# 01POWER.net
KiCad netlist of a schematic drawn in Altium Designer
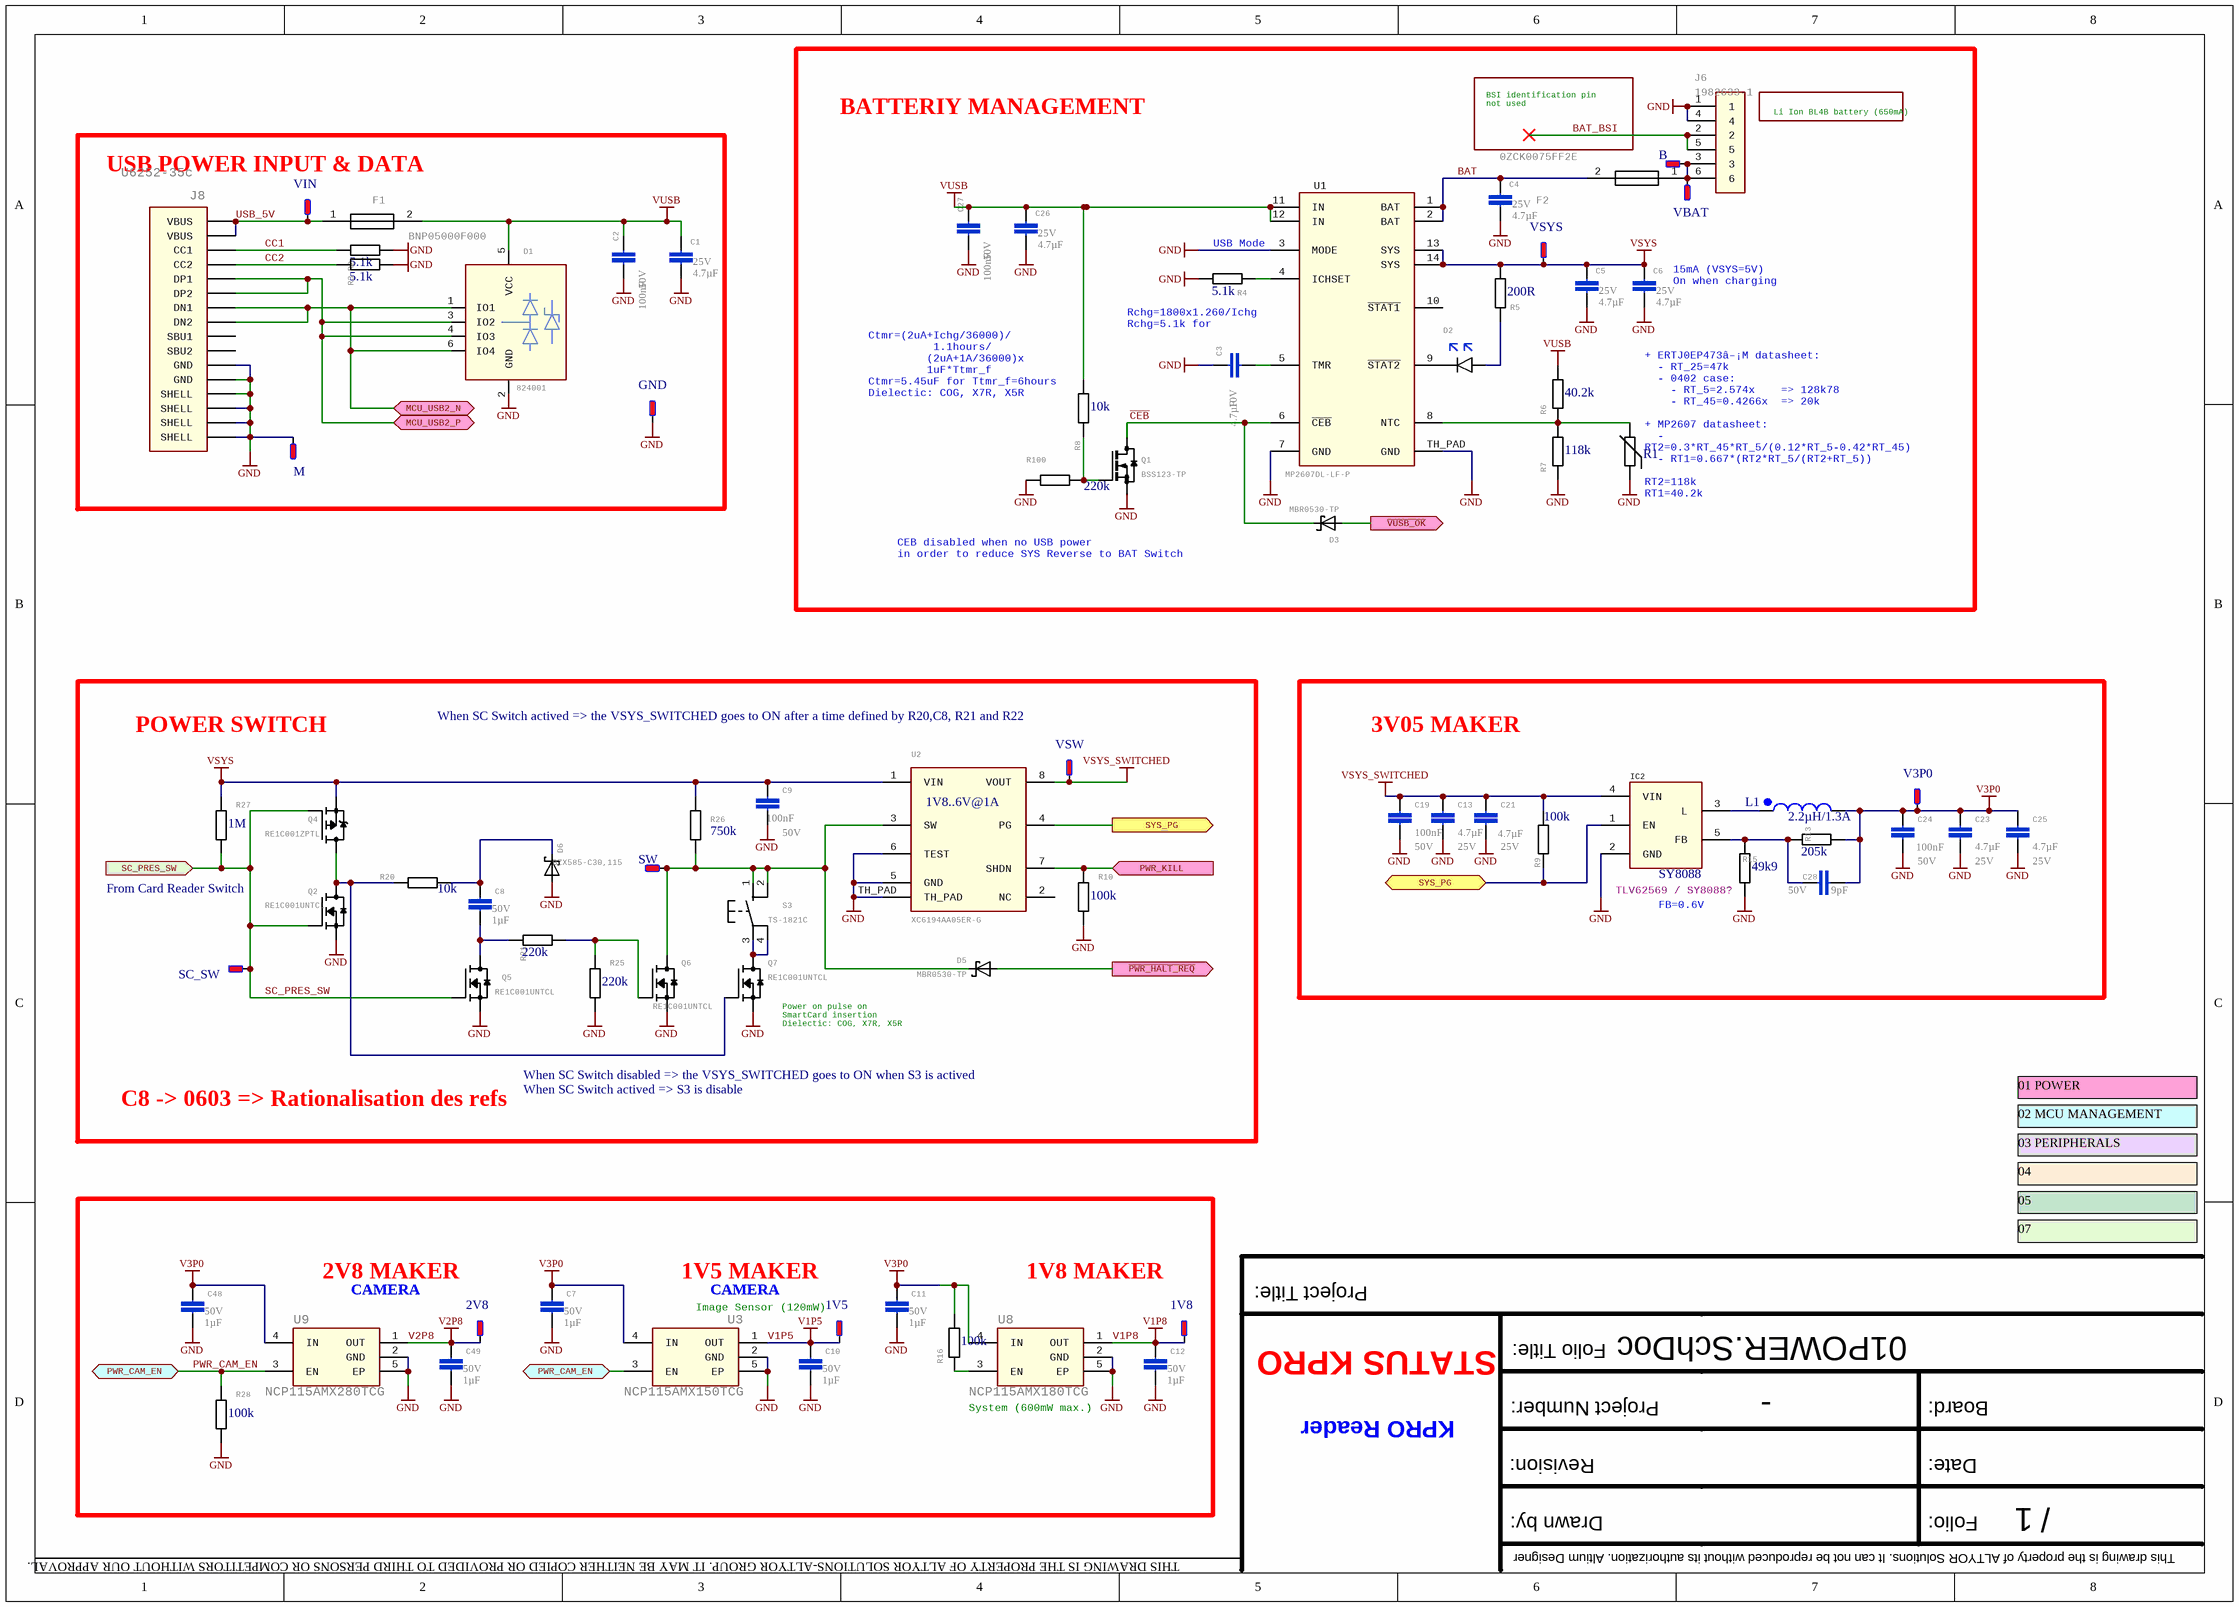
[diagram p0: 01POWER.SchDoc]

(export (version "E")
  (design (tool "Eeschema 10.0.6"))
  (components
    (comp (ref "1V5")
      (value "TP")
      (footprint "TESTPOINT 1MM")
      (description "Pointe de test 1.27mm")
      (libsource (lib "KCP-2282-600") (part "TP"))
    )
    (comp (ref "1V8")
      (value "TP")
      (footprint "TESTPOINT 1MM")
      (description "Pointe de test 1.27mm")
      (libsource (lib "KCP-2282-600") (part "TP"))
    )
    (comp (ref "2V8")
      (value "TP")
      (footprint "TESTPOINT 1MM")
      (description "Pointe de test 1.27mm")
      (libsource (lib "KCP-2282-600") (part "TP"))
    )
    (comp (ref "B")
      (value "TP")
      (footprint "PLAGE - ROUGE")
      (description "Pointe de test 1.27mm")
      (libsource (lib "KCP-2282-600") (part "TP"))
    )
    (comp (ref "C1")
      (value "0805X475M250CT")
      (footprint "0805 - CAPACITOR")
      (description "CAP X5R 4.7µF 25V ±10% 0805")
      (fields
        (field (name "MANUFACTURER") "WALSIN")
        (field (name "VOLTAGE") "25V")
        (field (name "NAME") "4.7µF")
      )
      (libsource (lib "KCP-2282-600") (part "C-EU-C4.7µF-X5R-6.3V-0805"))
    )
    (comp (ref "C2")
      (value "0402B104K500CT")
      (footprint "0402 - CAPACITOR")
      (description "CAP X7R 100nF 50V ±10% 0402")
      (fields
        (field (name "MANUFACTURER") "WALSIN")
        (field (name "VOLTAGE") "50V")
        (field (name "NAME") "100nF")
      )
      (libsource (lib "KCP-2282-600") (part "C-EU-C100NF-X7R-16V-0402"))
    )
    (comp (ref "C3")
      (value "CC0402KRX5R6BB475")
      (footprint "0402 - CAPACITOR")
      (description "CAP X5R 4.7µF 10V ±10% 0402")
      (fields
        (field (name "MANUFACTURER") "YAGEO")
        (field (name "VOLTAGE") "10V")
        (field (name "NAME") "4.7µF")
      )
      (libsource (lib "KCP-2282-600") (part "C-EU-C5UF-X7R-6.3V-0402"))
    )
    (comp (ref "C4")
      (value "0805X475M250CT")
      (footprint "0805 - CAPACITOR")
      (description "CAP X5R 4.7µF 25V ±10% 0805")
      (fields
        (field (name "MANUFACTURER") "WALSIN")
        (field (name "VOLTAGE") "25V")
        (field (name "NAME") "4.7µF")
      )
      (libsource (lib "KCP-2282-600") (part "C-EU-C4.7µF-X5R-6.3V-0805"))
    )
    (comp (ref "C5")
      (value "0805X475M250CT")
      (footprint "0805 - CAPACITOR")
      (description "CAP X5R 4.7µF 25V ±10% 0805")
      (fields
        (field (name "MANUFACTURER") "WALSIN")
        (field (name "VOLTAGE") "25V")
        (field (name "NAME") "4.7µF")
      )
      (libsource (lib "KCP-2282-600") (part "C-EU-C4.7µF-X5R-6.3V-0805"))
    )
    (comp (ref "C6")
      (value "0805X475M250CT")
      (footprint "0805 - CAPACITOR")
      (description "CAP X5R 4.7µF 25V ±10% 0805")
      (fields
        (field (name "MANUFACTURER") "WALSIN")
        (field (name "VOLTAGE") "25V")
        (field (name "NAME") "4.7µF")
      )
      (libsource (lib "KCP-2282-600") (part "C-EU-C4.7µF-X5R-6.3V-0805"))
    )
    (comp (ref "C7")
      (value "0603X105K500CT")
      (footprint "0603 - CAPACITOR")
      (description "CAP X5R 1µF 50V ±10% 0603")
      (fields
        (field (name "MANUFACTURER") "WALSIN")
        (field (name "VOLTAGE") "50V")
        (field (name "NAME") "1µF")
      )
      (libsource (lib "KCP-2282-600") (part "C-EU-C1µF-X5R-6.3V-0603"))
    )
    (comp (ref "C8")
      (value "0603X105K500CT")
      (footprint "0603 - CAPACITOR")
      (description "CAP X5R 1µF 50V ±10% 0603")
      (fields
        (field (name "MANUFACTURER") "WALSIN")
        (field (name "VOLTAGE") "50V")
        (field (name "NAME") "1µF")
      )
      (libsource (lib "KCP-2282-600") (part "C-EU-C1µF-X5R-6.3V-0603"))
    )
    (comp (ref "C9")
      (value "0402B104K500CT")
      (footprint "0402 - CAPACITOR")
      (description "CAP X7R 100nF 50V ±10% 0402")
      (fields
        (field (name "MANUFACTURER") "WALSIN")
        (field (name "VOLTAGE") "50V")
        (field (name "NAME") "100nF")
      )
      (libsource (lib "KCP-2282-600") (part "C-EU-C100NF-X7R-16V-0402"))
    )
    (comp (ref "C10")
      (value "0603X105K500CT")
      (footprint "0603 - CAPACITOR")
      (description "CAP X5R 1µF 50V ±10% 0603")
      (fields
        (field (name "MANUFACTURER") "WALSIN")
        (field (name "VOLTAGE") "50V")
        (field (name "NAME") "1µF")
      )
      (libsource (lib "KCP-2282-600") (part "C-EU-C1µF-X5R-6.3V-0603"))
    )
    (comp (ref "C11")
      (value "0603X105K500CT")
      (footprint "0603 - CAPACITOR")
      (description "CAP X5R 1µF 50V ±10% 0603")
      (fields
        (field (name "MANUFACTURER") "WALSIN")
        (field (name "VOLTAGE") "50V")
        (field (name "NAME") "1µF")
      )
      (libsource (lib "KCP-2282-600") (part "C-EU-C1µF-X5R-6.3V-0603"))
    )
    (comp (ref "C12")
      (value "0603X105K500CT")
      (footprint "0603 - CAPACITOR")
      (description "CAP X5R 1µF 50V ±10% 0603")
      (fields
        (field (name "MANUFACTURER") "WALSIN")
        (field (name "VOLTAGE") "50V")
        (field (name "NAME") "1µF")
      )
      (libsource (lib "KCP-2282-600") (part "C-EU-C1µF-X5R-6.3V-0603"))
    )
    (comp (ref "C13")
      (value "0805X475M250CT")
      (footprint "0805 - CAPACITOR")
      (description "CAP X5R 4.7µF 25V ±10% 0805")
      (fields
        (field (name "MANUFACTURER") "WALSIN")
        (field (name "VOLTAGE") "25V")
        (field (name "NAME") "4.7µF")
      )
      (libsource (lib "KCP-2282-600") (part "C-EU-C4.7µF-X5R-6.3V-0805"))
    )
    (comp (ref "C19")
      (value "0402B104K500CT")
      (footprint "0402 - CAPACITOR")
      (description "CAP X7R 100nF 50V ±10% 0402")
      (fields
        (field (name "MANUFACTURER") "WALSIN")
        (field (name "VOLTAGE") "50V")
        (field (name "NAME") "100nF")
      )
      (libsource (lib "KCP-2282-600") (part "C-EU-C100NF-X7R-16V-0402"))
    )
    (comp (ref "C21")
      (value "0805X475M250CT")
      (footprint "0805 - CAPACITOR")
      (description "CAP X5R 4.7µF 25V ±10% 0805")
      (fields
        (field (name "MANUFACTURER") "WALSIN")
        (field (name "VOLTAGE") "25V")
        (field (name "NAME") "4.7µF")
      )
      (libsource (lib "KCP-2282-600") (part "C-EU-C4.7µF-X5R-6.3V-0805"))
    )
    (comp (ref "C23")
      (value "0805X475M250CT")
      (footprint "0805 - CAPACITOR")
      (description "CAP X5R 4.7µF 25V ±10% 0805")
      (fields
        (field (name "MANUFACTURER") "WALSIN")
        (field (name "VOLTAGE") "25V")
        (field (name "NAME") "4.7µF")
      )
      (libsource (lib "KCP-2282-600") (part "C-EU-C4.7µF-X5R-6.3V-0805"))
    )
    (comp (ref "C24")
      (value "0402B104K500CT")
      (footprint "0402 - CAPACITOR")
      (description "CAP X7R 100nF 50V ±10% 0402")
      (fields
        (field (name "MANUFACTURER") "WALSIN")
        (field (name "VOLTAGE") "50V")
        (field (name "NAME") "100nF")
      )
      (libsource (lib "KCP-2282-600") (part "C-EU-C100NF-X7R-16V-0402"))
    )
    (comp (ref "C25")
      (value "0805X475M250CT")
      (footprint "0805 - CAPACITOR")
      (description "CAP X5R 4.7µF 25V ±10% 0805")
      (fields
        (field (name "MANUFACTURER") "WALSIN")
        (field (name "VOLTAGE") "25V")
        (field (name "NAME") "4.7µF")
      )
      (libsource (lib "KCP-2282-600") (part "C-EU-C4.7µF-X5R-6.3V-0805"))
    )
    (comp (ref "C26")
      (value "0805X475M250CT")
      (footprint "0805 - CAPACITOR")
      (description "CAP X5R 4.7µF 25V ±10% 0805")
      (fields
        (field (name "MANUFACTURER") "WALSIN")
        (field (name "VOLTAGE") "25V")
        (field (name "NAME") "4.7µF")
      )
      (libsource (lib "KCP-2282-600") (part "C-EU-C4.7µF-X5R-6.3V-0805"))
    )
    (comp (ref "C27")
      (value "0402B104K500CT")
      (footprint "0402 - CAPACITOR")
      (description "CAP X7R 100nF 50V ±10% 0402")
      (fields
        (field (name "MANUFACTURER") "WALSIN")
        (field (name "VOLTAGE") "50V")
        (field (name "NAME") "100nF")
      )
      (libsource (lib "KCP-2282-600") (part "C-EU-C100NF-X7R-16V-0402"))
    )
    (comp (ref "C28")
      (value "0402N9R0B500CT")
      (footprint "0402 - CAPACITOR")
      (description "CAP COG 9pF 50V ±0.1pF 0402")
      (fields
        (field (name "MANUFACTURER") "WALSIN")
        (field (name "VOLTAGE") "50V")
        (field (name "NAME") "9pF")
      )
      (libsource (lib "KCP-2282-600") (part "C-EU-C9PF-C0G-50V-0402"))
    )
    (comp (ref "C48")
      (value "0603X105K500CT")
      (footprint "0603 - CAPACITOR")
      (description "CAP X5R 1µF 50V ±10% 0603")
      (fields
        (field (name "MANUFACTURER") "WALSIN")
        (field (name "VOLTAGE") "50V")
        (field (name "NAME") "1µF")
      )
      (libsource (lib "KCP-2282-600") (part "C-EU-C1µF-X5R-6.3V-0603"))
    )
    (comp (ref "C49")
      (value "0603X105K500CT")
      (footprint "0603 - CAPACITOR")
      (description "CAP X5R 1µF 50V ±10% 0603")
      (fields
        (field (name "MANUFACTURER") "WALSIN")
        (field (name "VOLTAGE") "50V")
        (field (name "NAME") "1µF")
      )
      (libsource (lib "KCP-2282-600") (part "C-EU-C1µF-X5R-6.3V-0603"))
    )
    (comp (ref "D1")
      (value "824001")
      (footprint "SOT23-6 0.95 Var AA")
      (description "diode TVS, 82400 Series, Bidirectionelle")
      (fields (field (name "MANUFACTURER") "Würth"))
      (libsource (lib "KCP-2282-600") (part "824001"))
    )
    (comp (ref "D2")
      (value "LR_Y8SF-U1V2-1")
      (footprint "OSRAM LRY8SFU1V21")
      (description "Osram Opto Micro SIDELED Series Red LED, 120    Source:  Datasheet")
      (fields (field (name "MANUFACTURER") "OSRAM"))
      (libsource (lib "KCP-2282-600") (part "LR_Y8SF-U1V2-1"))
    )
    (comp (ref "D3")
      (value "MBR0530-TP")
      (footprint "SOD123 DIODE INC")
      (description "Schottky Rectifier, 30 V, 500 mA, Single")
      (fields (field (name "MANUFACTURER") "ON SEMI"))
      (libsource (lib "KCP-2282-600") (part "MBR0530T1G"))
    )
    (comp (ref "D5")
      (value "MBR0530-TP")
      (footprint "SOD123 DIODE INC")
      (description "Schottky Rectifier, 30 V, 500 mA, Single")
      (fields (field (name "MANUFACTURER") "ON SEMI"))
      (libsource (lib "KCP-2282-600") (part "MBR0530T1G"))
    )
    (comp (ref "D6")
      (value "BZX585-C30,115")
      (footprint "SOD523 TOSHIBA")
      (description "Zener 3V, 300mW - SOD 523-3")
      (fields (field (name "MANUFACTURER") "NXP"))
      (libsource (lib "KCP-2282-600") (part "MBR0530T1G"))
    )
    (comp (ref "F1")
      (value "BNP05000F000")
      (footprint "0805 - FUSE")
      (description "FUSE 500mA 6V 0805")
      (fields (field (name "MANUFACTURER") "JNHONGBAO"))
      (libsource (lib "KCP-2282-600") (part "0ZCK0050FF2E"))
    )
    (comp (ref "F2")
      (value "0ZCK0075FF2E")
      (footprint "0805 - FUSE")
      (fields (field (name "MANUFACTURER") "Bel Circuit Protection"))
      (libsource (lib "KCP-2282-600") (part "0ZCK0075FF2E"))
    )
    (comp (ref "GND")
      (value "TP")
      (footprint "TESTPOINT 1MM")
      (description "Pointe de test 1.27mm")
      (libsource (lib "KCP-2282-600") (part "TP"))
    )
    (comp (ref "IC2")
      (value "SY8088IAAC")
      (footprint "SOT23-5 0.95 Var AA")
      (description "DCDC 2V5..5V5  50µA 1V8..3V3")
      (fields (field (name "MANUFACTURER") "SILERGY") (field (name "NAME") "SY8088"))
      (libsource (lib "KCP-2282-600") (part "SILERGY SI8088IAAC"))
    )
    (comp (ref "J6")
      (value "1982633-1")
      (footprint "TE 19826331")
      (description "Connecteurs carte Ã  carte et mezzanine BATTERY CONN 3 POSITION")
      (fields (field (name "MANUFACTURER") "TE Connectivity"))
      (libsource (lib "KCP-2282-600") (part "1982633-1"))
    )
    (comp (ref "J8")
      (value "U6252-35c")
      (footprint "ANTENK U6252-35C")
      (description "Connecteurs USB USB C Rec 16P 3u\" Mid Mnt 1.6mm O-set SMT L = 6.5mm S-Spring")
      (fields (field (name "MANUFACTURER") "ANTENK"))
      (libsource (lib "KCP-2282-600") (part "ANTENK U6252-35c"))
    )
    (comp (ref "L1")
      (value "BWVF002520122R2M00")
      (footprint "CHILISON BWF00252012")
      (description "IND 2.2µH, 20%, 1.8A 68mOhm 1MHz - 2.5x2")
      (fields (field (name "MANUFACTURER") "CHILISIN") (field (name "NAME") "2.2µH/1.3A"))
      (libsource (lib "KCP-2282-600") (part "CDRH5D28NP-100NC"))
    )
    (comp (ref "M")
      (value "TP")
      (footprint "PLAGE - NOIRE")
      (description "Pointe de test 1.27mm")
      (libsource (lib "KCP-2282-600") (part "TP"))
    )
    (comp (ref "Q1")
      (value "BSS123-TP")
      (footprint "SOT23-VAR AB")
      (description "MOS N 100V 170mA Rds6R - SOT23")
      (fields (field (name "MANUFACTURER") "MCC"))
      (libsource (lib "KCP-2282-600") (part "BSS123"))
    )
    (comp (ref "Q2")
      (value "RE1C001UNTCL")
      (footprint "SOT-416-3")
      (description "MOS N 20V 100mA Rds3.5R")
      (fields (field (name "MANUFACTURER") "ROHM SEMI"))
      (libsource (lib "KCP-2282-600") (part "RE1C001UNTCL"))
    )
    (comp (ref "Q4")
      (value "RE1C001ZPTL")
      (footprint "SOT-416-3")
      (description "MOS P 20V 100mA Rds3.8R")
      (fields (field (name "MANUFACTURER") "ROHM SEMI"))
      (libsource (lib "KCP-2282-600") (part "RE1C001ZPTL"))
    )
    (comp (ref "Q5")
      (value "RE1C001UNTCL")
      (footprint "SOT-416-3")
      (description "MOS N 20V 100mA Rds3.5R")
      (fields (field (name "MANUFACTURER") "ROHM SEMI"))
      (libsource (lib "KCP-2282-600") (part "RE1C001UNTCL"))
    )
    (comp (ref "Q6")
      (value "RE1C001UNTCL")
      (footprint "SOT-416-3")
      (description "MOS N 20V 100mA Rds3.5R")
      (fields (field (name "MANUFACTURER") "ROHM SEMI"))
      (libsource (lib "KCP-2282-600") (part "RE1C001UNTCL"))
    )
    (comp (ref "Q7")
      (value "RE1C001UNTCL")
      (footprint "SOT-416-3")
      (description "MOS N 20V 100mA Rds3.5R")
      (fields (field (name "MANUFACTURER") "ROHM SEMI"))
      (libsource (lib "KCP-2282-600") (part "RE1C001UNTCL"))
    )
    (comp (ref "R1")
      (value "ERT-J0EP473GM")
      (footprint "0402 - RESISTOR")
      (description "CTN 47k 2% B(25/50) 4050K 0/+1% - 0402")
      (fields (field (name "MANUFACTURER") "PANASONIC"))
      (libsource (lib "KCP-2282-600") (part "ERT-J0EP473GM"))
    )
    (comp (ref "R2")
      (value "RC0402FR-075K1L")
      (footprint "0402 - RESISTOR")
      (description "RES 5.1k 63mW 1% 0402")
      (fields (field (name "MANUFACTURER") "YAGEO") (field (name "NAME") "5.1k"))
      (libsource (lib "KCP-2282-600") (part "R-EU-R5.1K-1%-0402"))
    )
    (comp (ref "R3")
      (value "RC0402FR-075K1L")
      (footprint "0402 - RESISTOR")
      (description "RES 5.1k 63mW 1% 0402")
      (fields (field (name "MANUFACTURER") "YAGEO") (field (name "NAME") "5.1k"))
      (libsource (lib "KCP-2282-600") (part "R-EU-R5.1K-1%-0402"))
    )
    (comp (ref "R4")
      (value "RC0402FR-075K1L")
      (footprint "0402 - RESISTOR")
      (description "RES 5.1k 63mW 1% 0402")
      (fields (field (name "MANUFACTURER") "YAGEO") (field (name "NAME") "5.1k"))
      (libsource (lib "KCP-2282-600") (part "R-EU-R4.53K-1%-0402"))
    )
    (comp (ref "R5")
      (value "RC0402FR-07200RL")
      (footprint "0402 - RESISTOR")
      (description "RES 200R 63mW 1% 0402")
      (fields (field (name "MANUFACTURER") "YAGEO") (field (name "NAME") "200R"))
      (libsource (lib "KCP-2282-600") (part "R-EU-R200-1%-0402"))
    )
    (comp (ref "R6")
      (value "RC0402FR-0740K2L")
      (footprint "0402 - RESISTOR")
      (description "RES 40.2k 63mW 1% 0402")
      (fields (field (name "MANUFACTURER") "YAGEO") (field (name "NAME") "40.2k"))
      (libsource (lib "KCP-2282-600") (part "R-EU-R40.2K-1%-0402"))
    )
    (comp (ref "R7")
      (value "RC0402FR-07118KL")
      (footprint "0402 - RESISTOR")
      (description "RES 118k 63mW 1% 0402")
      (fields (field (name "MANUFACTURER") "YAGEO") (field (name "NAME") "118k"))
      (libsource (lib "KCP-2282-600") (part "R-EU-R118K-1%-0402"))
    )
    (comp (ref "R8")
      (value "RC0402FR-0710KL")
      (footprint "0402 - RESISTOR")
      (description "RES 10k 63mW 1% 0402")
      (fields (field (name "MANUFACTURER") "YAGEO") (field (name "NAME") "10k"))
      (libsource (lib "KCP-2282-600") (part "R-EU-R10K-1%-0402"))
    )
    (comp (ref "R9")
      (value "RC0402FR-07100KL")
      (footprint "0402 - RESISTOR")
      (description "RES 100k 63mW 1% 0402")
      (fields (field (name "MANUFACTURER") "YAGEO") (field (name "NAME") "100k"))
      (libsource (lib "KCP-2282-600") (part "R-EU-R100K-1%-0402"))
    )
    (comp (ref "R10")
      (value "RC0402FR-07100KL")
      (footprint "0402 - RESISTOR")
      (description "RES 100k 63mW 1% 0402")
      (fields (field (name "MANUFACTURER") "YAGEO") (field (name "NAME") "100k"))
      (libsource (lib "KCP-2282-600") (part "R-EU-R100K-1%-0402"))
    )
    (comp (ref "R13")
      (value "RC0402FR-07205KL")
      (footprint "0402 - RESISTOR")
      (description "RES 205k 63mW 1% 0402")
      (fields (field (name "MANUFACTURER") "YAGEO") (field (name "NAME") "205k"))
      (libsource (lib "KCP-2282-600") (part "R-EU-R100K-1%-0402"))
    )
    (comp (ref "R15")
      (value "RC0402FR-0749K9L")
      (footprint "0402 - RESISTOR")
      (description "RES 49k9 63mW 1% 0402")
      (fields (field (name "MANUFACTURER") "YAGEO") (field (name "NAME") "49k9"))
      (libsource (lib "KCP-2282-600") (part "R-EU-R100K-1%-0402"))
    )
    (comp (ref "R16")
      (value "RC0402FR-07100KL")
      (footprint "0402 - RESISTOR")
      (description "RES 100k 63mW 1% 0402")
      (fields (field (name "MANUFACTURER") "YAGEO") (field (name "NAME") "100k"))
      (libsource (lib "KCP-2282-600") (part "R-EU-R100K-1%-0402"))
    )
    (comp (ref "R20")
      (value "RC0402FR-0710KL")
      (footprint "0402 - RESISTOR")
      (description "RES 10k 63mW 1% 0402")
      (fields (field (name "MANUFACTURER") "YAGEO") (field (name "NAME") "10k"))
      (libsource (lib "KCP-2282-600") (part "R-EU-R10K-1%-0402"))
    )
    (comp (ref "R21")
      (value "RC0402FR-07220KL")
      (footprint "0402 - RESISTOR")
      (description "RES 220k 63mW 1% 0402")
      (fields (field (name "MANUFACTURER") "YAGEO") (field (name "NAME") "220k"))
      (libsource (lib "KCP-2282-600") (part "R-EU-R220K-1%-0402"))
    )
    (comp (ref "R25")
      (value "RC0402FR-07220KL")
      (footprint "0402 - RESISTOR")
      (description "RES 220k 63mW 1% 0402")
      (fields (field (name "MANUFACTURER") "YAGEO") (field (name "NAME") "220k"))
      (libsource (lib "KCP-2282-600") (part "R-EU-R220K-1%-0402"))
    )
    (comp (ref "R26")
      (value "RC0402FR-07750KL")
      (footprint "0402 - RESISTOR")
      (description "RES 750k 63mW 1% 0402")
      (fields (field (name "MANUFACTURER") "YAGEO") (field (name "NAME") "750k"))
      (libsource (lib "KCP-2282-600") (part "R-EU-R750K-1%-0402"))
    )
    (comp (ref "R27")
      (value "RC0201FR-071ML")
      (footprint "0402 - RESISTOR")
      (description "RES 1M 63mW 1% 0402")
      (fields (field (name "MANUFACTURER") "YAGEO") (field (name "NAME") "1M"))
      (libsource (lib "KCP-2282-600") (part "R-EU-R1M-1%-0402"))
    )
    (comp (ref "R28")
      (value "RC0402FR-07100KL")
      (footprint "0402 - RESISTOR")
      (description "RES 100k 63mW 1% 0402")
      (fields (field (name "MANUFACTURER") "YAGEO") (field (name "NAME") "100k"))
      (libsource (lib "KCP-2282-600") (part "R-EU-R100K-1%-0402"))
    )
    (comp (ref "R100")
      (value "RC0402FR-07220KL")
      (footprint "0402 - RESISTOR")
      (description "RES 220k 63mW 1% 0402")
      (fields (field (name "MANUFACTURER") "YAGEO") (field (name "NAME") "220k"))
      (libsource (lib "KCP-2282-600") (part "R-EU-R220K-1%-0402"))
    )
    (comp (ref "S3")
      (value "TS-1821C")
      (footprint "SONG TS1821C")
      (description "Interrupteurs de contact WS-TASU SMD Switch 3.5x2.9 x1.35mm")
      (fields (field (name "MANUFACTURER") "SONG"))
      (libsource (lib "KCP-2282-600") (part "434331013822"))
    )
    (comp (ref "SC_SW")
      (value "TP")
      (footprint "TESTPOINT 1MM")
      (description "Pointe de test 1.27mm")
      (libsource (lib "KCP-2282-600") (part "TP"))
    )
    (comp (ref "SW")
      (value "TP")
      (footprint "TESTPOINT 1MM")
      (description "Pointe de test 1.27mm")
      (libsource (lib "KCP-2282-600") (part "TP"))
    )
    (comp (ref "U1")
      (value "MP2607DL-LF-P")
      (footprint "QFN14-0.5-3s4")
      (description "Li + LINEAR Charger WithSystem Power Path Management")
      (fields (field (name "MANUFACTURER") "MPS"))
      (libsource (lib "KCP-2282-600") (part "MP2607DL-LF-P"))
    )
    (comp (ref "U2")
      (value "XC6194AA05ER-G")
      (footprint "TOREX USP-8B06")
      (description "Power saving Push Button Load switch")
      (fields (field (name "MANUFACTURER") "TOREX"))
      (libsource (lib "KCP-2282-600") (part "XC6194AA05ER-G"))
    )
    (comp (ref "U3")
      (value "NCP115AMX150TCG")
      (footprint "ON SEMI NCV8160AMX330TBG")
      (description "LDO Regulator - High PSRR - 300mA - Input Voltage 1.7V/5.5V - Ouput Voltage 1.5V")
      (fields (field (name "MANUFACTURER") "ON SEMI"))
      (libsource (lib "KCP-2282-600") (part "NCP115AMX150TCG"))
    )
    (comp (ref "U8")
      (value "NCP115AMX180TCG")
      (footprint "ON SEMI NCV8160AMX330TBG")
      (description "LDO Regulator - High PSRR - 300mA - Input Voltage 1.7V/5.5V - Ouput Voltage 1.8V")
      (fields (field (name "MANUFACTURER") "ON SEMI"))
      (libsource (lib "KCP-2282-600") (part "NCP115AMX180TCG"))
    )
    (comp (ref "U9")
      (value "NCP115AMX280TCG")
      (footprint "ON SEMI NCV8160AMX330TBG")
      (description "LDO Regulator - High PSRR - 300mA - Input Voltage 1.7V/5.5V - Ouput Voltage 2.8V")
      (fields (field (name "MANUFACTURER") "ON SEMI"))
      (libsource (lib "KCP-2282-600") (part "NCP115AMX280TCG"))
    )
    (comp (ref "V3P0")
      (value "TP")
      (footprint "TESTPOINT 1MM")
      (description "Pointe de test 1.27mm")
      (libsource (lib "KCP-2282-600") (part "TP"))
    )
    (comp (ref "VBAT")
      (value "TP")
      (footprint "TESTPOINT 1MM")
      (description "Pointe de test 1.27mm")
      (libsource (lib "KCP-2282-600") (part "TP"))
    )
    (comp (ref "VIN")
      (value "TP")
      (footprint "TESTPOINT 1MM")
      (description "Pointe de test 1.27mm")
      (libsource (lib "KCP-2282-600") (part "TP"))
    )
    (comp (ref "VSW")
      (value "TP")
      (footprint "TESTPOINT 1MM")
      (description "Pointe de test 1.27mm")
      (libsource (lib "KCP-2282-600") (part "TP"))
    )
    (comp (ref "VSYS")
      (value "TP")
      (footprint "TESTPOINT 1MM")
      (description "Pointe de test 1.27mm")
      (libsource (lib "KCP-2282-600") (part "TP"))
    )
  )
  (nets
    (net (code "1") (name "/BAT") (class "Default")
      (node (ref "C4") (pin "1") (pinfunction "1_1") (pintype "passive"))
      (node (ref "F2") (pin "2") (pinfunction "2_2") (pintype "passive"))
      (node (ref "U1") (pin "1") (pinfunction "BAT_1") (pintype "passive"))
      (node (ref "U1") (pin "2") (pinfunction "BAT_2") (pintype "passive"))
    )
    (net (code "2") (name "/BAT_BSI") (class "Default")
      (node (ref "J6") (pin "2") (pinfunction "2_2") (pintype "passive"))
      (node (ref "J6") (pin "5") (pinfunction "5_5") (pintype "passive"))
    )
    (net (code "3") (name "/CC1") (class "Default")
      (node (ref "J8") (pin "A5") (pinfunction "CC1_A5") (pintype "passive"))
      (node (ref "R2") (pin "2") (pinfunction "2_2") (pintype "passive"))
    )
    (net (code "4") (name "/CC2") (class "Default")
      (node (ref "J8") (pin "B5") (pinfunction "CC2_B5") (pintype "passive"))
      (node (ref "R3") (pin "2") (pinfunction "2_2") (pintype "passive"))
    )
    (net (code "5") (name "/MCU_USB2_N") (class "Default")
      (node (ref "D1") (pin "1") (pinfunction "IO1_1") (pintype "passive"))
      (node (ref "D1") (pin "6") (pinfunction "IO4_6") (pintype "passive"))
      (node (ref "J8") (pin "A7") (pinfunction "DN1_A7") (pintype "passive"))
      (node (ref "J8") (pin "B7") (pinfunction "DN2_B7") (pintype "passive"))
    )
    (net (code "6") (name "/MCU_USB2_P") (class "Default")
      (node (ref "D1") (pin "3") (pinfunction "IO2_3") (pintype "passive"))
      (node (ref "D1") (pin "4") (pinfunction "IO3_4") (pintype "passive"))
      (node (ref "J8") (pin "A6") (pinfunction "DP1_A6") (pintype "passive"))
      (node (ref "J8") (pin "B6") (pinfunction "DP2_B6") (pintype "passive"))
    )
    (net (code "7") (name "/PWR_CAM_EN") (class "Default")
      (node (ref "R28") (pin "2") (pinfunction "2_2") (pintype "passive"))
      (node (ref "U3") (pin "3") (pinfunction "EN_3") (pintype "passive"))
      (node (ref "U9") (pin "3") (pinfunction "EN_3") (pintype "passive"))
    )
    (net (code "8") (name "/PWR_KILL") (class "Default")
      (node (ref "R10") (pin "2") (pinfunction "2_2") (pintype "passive"))
      (node (ref "U2") (pin "7") (pinfunction "SHDN_7") (pintype "passive"))
    )
    (net (code "9") (name "/SC_PRES_SW") (class "Default")
      (node (ref "Q2") (pin "1") (pinfunction "G_1") (pintype "passive"))
      (node (ref "Q4") (pin "1") (pinfunction "G_1") (pintype "passive"))
      (node (ref "Q5") (pin "1") (pinfunction "G_1") (pintype "passive"))
      (node (ref "R27") (pin "1") (pinfunction "1_1") (pintype "passive"))
      (node (ref "SC_SW") (pin "1") (pinfunction "PT_1") (pintype "passive"))
    )
    (net (code "10") (name "/SYS_PG") (class "Default")
      (node (ref "IC2") (pin "1") (pinfunction "EN_1") (pintype "passive"))
      (node (ref "R9") (pin "2") (pinfunction "2_2") (pintype "passive"))
      (node (ref "U2") (pin "4") (pinfunction "PG_4") (pintype "passive"))
    )
    (net (code "11") (name "/USB_5V") (class "Default")
      (node (ref "F1") (pin "1") (pinfunction "1_1") (pintype "passive"))
      (node (ref "J8") (pin "A4_B9") (pinfunction "VBUS_A4_B9") (pintype "passive"))
      (node (ref "J8") (pin "B4_A9") (pinfunction "VBUS_B4_A9") (pintype "passive"))
      (node (ref "VIN") (pin "1") (pinfunction "PT_1") (pintype "passive"))
    )
    (net (code "12") (name "/~{CEB}") (class "Default")
      (node (ref "D3") (pin "C") (pinfunction "C_C") (pintype "passive"))
      (node (ref "Q1") (pin "3") (pinfunction "D_3") (pintype "passive"))
      (node (ref "U1") (pin "6") (pinfunction "~{CEB}_6") (pintype "passive"))
    )
    (net (code "13") (name "/~{PWR_HALT_REQ}") (class "Default")
      (node (ref "D5") (pin "A") (pinfunction "A_A") (pintype "passive"))
    )
    (net (code "14") (name "/~{VUSB_OK}") (class "Default")
      (node (ref "D3") (pin "A") (pinfunction "A_A") (pintype "passive"))
    )
    (net (code "15") (name "GND") (class "Default")
      (node (ref "C1") (pin "2") (pinfunction "2_2") (pintype "passive"))
      (node (ref "C10") (pin "2") (pinfunction "2_2") (pintype "passive"))
      (node (ref "C11") (pin "2") (pinfunction "2_2") (pintype "passive"))
      (node (ref "C12") (pin "2") (pinfunction "2_2") (pintype "passive"))
      (node (ref "C13") (pin "2") (pinfunction "2_2") (pintype "passive"))
      (node (ref "C19") (pin "2") (pinfunction "2_2") (pintype "passive"))
      (node (ref "C2") (pin "2") (pinfunction "2_2") (pintype "passive"))
      (node (ref "C21") (pin "2") (pinfunction "2_2") (pintype "passive"))
      (node (ref "C23") (pin "2") (pinfunction "2_2") (pintype "passive"))
      (node (ref "C24") (pin "2") (pinfunction "2_2") (pintype "passive"))
      (node (ref "C25") (pin "2") (pinfunction "2_2") (pintype "passive"))
      (node (ref "C26") (pin "2") (pinfunction "2_2") (pintype "passive"))
      (node (ref "C27") (pin "2") (pinfunction "2_2") (pintype "passive"))
      (node (ref "C3") (pin "1") (pinfunction "1_1") (pintype "passive"))
      (node (ref "C4") (pin "2") (pinfunction "2_2") (pintype "passive"))
      (node (ref "C48") (pin "2") (pinfunction "2_2") (pintype "passive"))
      (node (ref "C49") (pin "2") (pinfunction "2_2") (pintype "passive"))
      (node (ref "C5") (pin "2") (pinfunction "2_2") (pintype "passive"))
      (node (ref "C6") (pin "2") (pinfunction "2_2") (pintype "passive"))
      (node (ref "C7") (pin "2") (pinfunction "2_2") (pintype "passive"))
      (node (ref "C9") (pin "2") (pinfunction "2_2") (pintype "passive"))
      (node (ref "D1") (pin "2") (pinfunction "GND_2") (pintype "passive"))
      (node (ref "D6") (pin "A") (pinfunction "A_A") (pintype "passive"))
      (node (ref "GND") (pin "1") (pinfunction "PT_1") (pintype "passive"))
      (node (ref "IC2") (pin "2") (pinfunction "GND_2") (pintype "passive"))
      (node (ref "J6") (pin "1") (pinfunction "1_1") (pintype "passive"))
      (node (ref "J6") (pin "4") (pinfunction "4_4") (pintype "passive"))
      (node (ref "J8") (pin "A1_B12") (pinfunction "GND_A1_B12") (pintype "passive"))
      (node (ref "J8") (pin "B1_A12") (pinfunction "GND_B1_A12") (pintype "passive"))
      (node (ref "J8") (pin "S1") (pinfunction "SHELL_S1") (pintype "passive"))
      (node (ref "J8") (pin "S2") (pinfunction "SHELL_S2") (pintype "passive"))
      (node (ref "J8") (pin "S3") (pinfunction "SHELL_S3") (pintype "passive"))
      (node (ref "J8") (pin "S4") (pinfunction "SHELL_S4") (pintype "passive"))
      (node (ref "M") (pin "1") (pinfunction "PT_1") (pintype "passive"))
      (node (ref "Q1") (pin "2") (pinfunction "S_2") (pintype "passive"))
      (node (ref "Q2") (pin "2") (pinfunction "S_2") (pintype "passive"))
      (node (ref "Q5") (pin "2") (pinfunction "S_2") (pintype "passive"))
      (node (ref "Q6") (pin "2") (pinfunction "S_2") (pintype "passive"))
      (node (ref "Q7") (pin "2") (pinfunction "S_2") (pintype "passive"))
      (node (ref "R1") (pin "1") (pinfunction "1_1") (pintype "passive"))
      (node (ref "R10") (pin "1") (pinfunction "1_1") (pintype "passive"))
      (node (ref "R100") (pin "1") (pinfunction "1_1") (pintype "passive"))
      (node (ref "R15") (pin "1") (pinfunction "1_1") (pintype "passive"))
      (node (ref "R2") (pin "1") (pinfunction "1_1") (pintype "passive"))
      (node (ref "R25") (pin "1") (pinfunction "1_1") (pintype "passive"))
      (node (ref "R28") (pin "1") (pinfunction "1_1") (pintype "passive"))
      (node (ref "R3") (pin "1") (pinfunction "1_1") (pintype "passive"))
      (node (ref "R4") (pin "2") (pinfunction "2_2") (pintype "passive"))
      (node (ref "R7") (pin "1") (pinfunction "1_1") (pintype "passive"))
      (node (ref "U1") (pin "3") (pinfunction "MODE_3") (pintype "passive"))
      (node (ref "U1") (pin "7") (pinfunction "GND_7") (pintype "passive"))
      (node (ref "U1") (pin "TH_PAD") (pinfunction "GND_TH_PAD") (pintype "passive"))
      (node (ref "U2") (pin "5") (pinfunction "GND_5") (pintype "passive"))
      (node (ref "U2") (pin "6") (pinfunction "TEST_6") (pintype "passive"))
      (node (ref "U2") (pin "TH_PAD") (pinfunction "TH_PAD_TH_PAD") (pintype "passive"))
      (node (ref "U3") (pin "2") (pinfunction "GND_2") (pintype "passive"))
      (node (ref "U3") (pin "5") (pinfunction "EP_5") (pintype "passive"))
      (node (ref "U8") (pin "2") (pinfunction "GND_2") (pintype "passive"))
      (node (ref "U8") (pin "5") (pinfunction "EP_5") (pintype "passive"))
      (node (ref "U9") (pin "2") (pinfunction "GND_2") (pintype "passive"))
      (node (ref "U9") (pin "5") (pinfunction "EP_5") (pintype "passive"))
    )
    (net (code "16") (name "Net-(B-PT)") (class "Default")
      (node (ref "B") (pin "1") (pinfunction "PT_1") (pintype "passive"))
      (node (ref "F2") (pin "1") (pinfunction "1_1") (pintype "passive"))
      (node (ref "J6") (pin "3") (pinfunction "3_3") (pintype "passive"))
      (node (ref "J6") (pin "6") (pinfunction "6_6") (pintype "passive"))
      (node (ref "VBAT") (pin "1") (pinfunction "PT_1") (pintype "passive"))
    )
    (net (code "17") (name "Net-(C8-Pad1)") (class "Default")
      (node (ref "C8") (pin "1") (pinfunction "1_1") (pintype "passive"))
      (node (ref "D6") (pin "C") (pinfunction "C_C") (pintype "passive"))
      (node (ref "R20") (pin "2") (pinfunction "2_2") (pintype "passive"))
    )
    (net (code "18") (name "Net-(D2-A)") (class "Default")
      (node (ref "D2") (pin "2") (pinfunction "A_2") (pintype "passive"))
      (node (ref "R5") (pin "2") (pinfunction "2_2") (pintype "passive"))
    )
    (net (code "19") (name "Net-(D2-C)") (class "Default")
      (node (ref "D2") (pin "1") (pinfunction "C_1") (pintype "passive"))
      (node (ref "U1") (pin "9") (pinfunction "~{STAT2}_9") (pintype "passive"))
    )
    (net (code "20") (name "Net-(IC2-FB)") (class "Default")
      (node (ref "C28") (pin "1") (pinfunction "1_1") (pintype "passive"))
      (node (ref "IC2") (pin "5") (pinfunction "FB_5") (pintype "passive"))
      (node (ref "R13") (pin "2") (pinfunction "2_2") (pintype "passive"))
      (node (ref "R15") (pin "2") (pinfunction "2_2") (pintype "passive"))
    )
    (net (code "21") (name "Net-(IC2-L)") (class "Default")
      (node (ref "IC2") (pin "3") (pinfunction "L_3") (pintype "passive"))
      (node (ref "L1") (pin "1") (pinfunction "1_1") (pintype "passive"))
    )
    (net (code "22") (name "Net-(Q1-G)") (class "Default")
      (node (ref "Q1") (pin "1") (pinfunction "G_1") (pintype "passive"))
      (node (ref "R100") (pin "2") (pinfunction "2_2") (pintype "passive"))
      (node (ref "R8") (pin "1") (pinfunction "1_1") (pintype "passive"))
    )
    (net (code "23") (name "Net-(Q2-D)") (class "Default")
      (node (ref "Q2") (pin "3") (pinfunction "D_3") (pintype "passive"))
      (node (ref "Q4") (pin "3") (pinfunction "D_3") (pintype "passive"))
      (node (ref "Q7") (pin "1") (pinfunction "G_1") (pintype "passive"))
      (node (ref "R20") (pin "1") (pinfunction "1_1") (pintype "passive"))
    )
    (net (code "24") (name "Net-(Q5-D)") (class "Default")
      (node (ref "C8") (pin "2") (pinfunction "2_2") (pintype "passive"))
      (node (ref "Q5") (pin "3") (pinfunction "D_3") (pintype "passive"))
      (node (ref "R21") (pin "2") (pinfunction "2_2") (pintype "passive"))
    )
    (net (code "25") (name "Net-(Q6-D)") (class "Default")
      (node (ref "D5") (pin "C") (pinfunction "C_C") (pintype "passive"))
      (node (ref "Q6") (pin "3") (pinfunction "D_3") (pintype "passive"))
      (node (ref "R26") (pin "1") (pinfunction "1_1") (pintype "passive"))
      (node (ref "S3") (pin "1") (pinfunction "S_1") (pintype "passive"))
      (node (ref "S3") (pin "2") (pinfunction "S1_2") (pintype "passive"))
      (node (ref "SW") (pin "1") (pinfunction "PT_1") (pintype "passive"))
      (node (ref "U2") (pin "3") (pinfunction "SW_3") (pintype "passive"))
    )
    (net (code "26") (name "Net-(Q6-G)") (class "Default")
      (node (ref "Q6") (pin "1") (pinfunction "G_1") (pintype "passive"))
      (node (ref "R21") (pin "1") (pinfunction "1_1") (pintype "passive"))
      (node (ref "R25") (pin "2") (pinfunction "2_2") (pintype "passive"))
    )
    (net (code "27") (name "Net-(Q7-D)") (class "Default")
      (node (ref "Q7") (pin "3") (pinfunction "D_3") (pintype "passive"))
      (node (ref "S3") (pin "3") (pinfunction "P_3") (pintype "passive"))
      (node (ref "S3") (pin "4") (pinfunction "P1_4") (pintype "passive"))
    )
    (net (code "28") (name "Net-(U1-ICHSET)") (class "Default")
      (node (ref "R4") (pin "1") (pinfunction "1_1") (pintype "passive"))
      (node (ref "U1") (pin "4") (pinfunction "ICHSET_4") (pintype "passive"))
    )
    (net (code "29") (name "Net-(U1-NTC)") (class "Default")
      (node (ref "R1") (pin "2") (pinfunction "2_2") (pintype "passive"))
      (node (ref "R6") (pin "1") (pinfunction "1_1") (pintype "passive"))
      (node (ref "R7") (pin "2") (pinfunction "2_2") (pintype "passive"))
      (node (ref "U1") (pin "8") (pinfunction "NTC_8") (pintype "passive"))
    )
    (net (code "30") (name "Net-(U1-TMR)") (class "Default")
      (node (ref "C3") (pin "2") (pinfunction "2_2") (pintype "passive"))
      (node (ref "U1") (pin "5") (pinfunction "TMR_5") (pintype "passive"))
    )
    (net (code "31") (name "Net-(U8-EN)") (class "Default")
      (node (ref "R16") (pin "2") (pinfunction "2_2") (pintype "passive"))
      (node (ref "U8") (pin "3") (pinfunction "EN_3") (pintype "passive"))
    )
    (net (code "32") (name "V1P5") (class "Default")
      (node (ref "1V5") (pin "1") (pinfunction "PT_1") (pintype "passive"))
      (node (ref "C10") (pin "1") (pinfunction "1_1") (pintype "passive"))
      (node (ref "U3") (pin "1") (pinfunction "OUT_1") (pintype "passive"))
    )
    (net (code "33") (name "V1P8") (class "Default")
      (node (ref "1V8") (pin "1") (pinfunction "PT_1") (pintype "passive"))
      (node (ref "C12") (pin "1") (pinfunction "1_1") (pintype "passive"))
      (node (ref "U8") (pin "1") (pinfunction "OUT_1") (pintype "passive"))
    )
    (net (code "34") (name "V2P8") (class "Default")
      (node (ref "2V8") (pin "1") (pinfunction "PT_1") (pintype "passive"))
      (node (ref "C49") (pin "1") (pinfunction "1_1") (pintype "passive"))
      (node (ref "U9") (pin "1") (pinfunction "OUT_1") (pintype "passive"))
    )
    (net (code "35") (name "V3P0") (class "Default")
      (node (ref "C11") (pin "1") (pinfunction "1_1") (pintype "passive"))
      (node (ref "C23") (pin "1") (pinfunction "1_1") (pintype "passive"))
      (node (ref "C24") (pin "1") (pinfunction "1_1") (pintype "passive"))
      (node (ref "C25") (pin "1") (pinfunction "1_1") (pintype "passive"))
      (node (ref "C28") (pin "2") (pinfunction "2_2") (pintype "passive"))
      (node (ref "C48") (pin "1") (pinfunction "1_1") (pintype "passive"))
      (node (ref "C7") (pin "1") (pinfunction "1_1") (pintype "passive"))
      (node (ref "L1") (pin "2") (pinfunction "2_2") (pintype "passive"))
      (node (ref "R13") (pin "1") (pinfunction "1_1") (pintype "passive"))
      (node (ref "R16") (pin "1") (pinfunction "1_1") (pintype "passive"))
      (node (ref "U3") (pin "4") (pinfunction "IN_4") (pintype "passive"))
      (node (ref "U8") (pin "4") (pinfunction "IN_4") (pintype "passive"))
      (node (ref "U9") (pin "4") (pinfunction "IN_4") (pintype "passive"))
      (node (ref "V3P0") (pin "1") (pinfunction "PT_1") (pintype "passive"))
    )
    (net (code "36") (name "VSYS") (class "Default")
      (node (ref "C5") (pin "1") (pinfunction "1_1") (pintype "passive"))
      (node (ref "C6") (pin "1") (pinfunction "1_1") (pintype "passive"))
      (node (ref "C9") (pin "1") (pinfunction "1_1") (pintype "passive"))
      (node (ref "Q4") (pin "2") (pinfunction "S_2") (pintype "passive"))
      (node (ref "R26") (pin "2") (pinfunction "2_2") (pintype "passive"))
      (node (ref "R27") (pin "2") (pinfunction "2_2") (pintype "passive"))
      (node (ref "R5") (pin "1") (pinfunction "1_1") (pintype "passive"))
      (node (ref "U1") (pin "13") (pinfunction "SYS_13") (pintype "passive"))
      (node (ref "U1") (pin "14") (pinfunction "SYS_14") (pintype "passive"))
      (node (ref "U2") (pin "1") (pinfunction "VIN_1") (pintype "passive"))
      (node (ref "VSYS") (pin "1") (pinfunction "PT_1") (pintype "passive"))
    )
    (net (code "37") (name "VSYS_SWITCHED") (class "Default")
      (node (ref "C13") (pin "1") (pinfunction "1_1") (pintype "passive"))
      (node (ref "C19") (pin "1") (pinfunction "1_1") (pintype "passive"))
      (node (ref "C21") (pin "1") (pinfunction "1_1") (pintype "passive"))
      (node (ref "IC2") (pin "4") (pinfunction "VIN_4") (pintype "passive"))
      (node (ref "R9") (pin "1") (pinfunction "1_1") (pintype "passive"))
      (node (ref "U2") (pin "8") (pinfunction "VOUT_8") (pintype "passive"))
      (node (ref "VSW") (pin "1") (pinfunction "PT_1") (pintype "passive"))
    )
    (net (code "38") (name "VUSB") (class "Default")
      (node (ref "C1") (pin "1") (pinfunction "1_1") (pintype "passive"))
      (node (ref "C2") (pin "1") (pinfunction "1_1") (pintype "passive"))
      (node (ref "C26") (pin "1") (pinfunction "1_1") (pintype "passive"))
      (node (ref "C27") (pin "1") (pinfunction "1_1") (pintype "passive"))
      (node (ref "D1") (pin "5") (pinfunction "VCC_5") (pintype "passive"))
      (node (ref "F1") (pin "2") (pinfunction "2_2") (pintype "passive"))
      (node (ref "R6") (pin "2") (pinfunction "2_2") (pintype "passive"))
      (node (ref "R8") (pin "2") (pinfunction "2_2") (pintype "passive"))
      (node (ref "U1") (pin "11") (pinfunction "IN_11") (pintype "passive"))
      (node (ref "U1") (pin "12") (pinfunction "IN_12") (pintype "passive"))
    )
    (net (code "39") (name "unconnected-(J8-SBU1-PadA8)") (class "Default")
      (node (ref "J8") (pin "A8") (pinfunction "SBU1_A8") (pintype "passive"))
    )
    (net (code "40") (name "unconnected-(J8-SBU2-PadB8)") (class "Default")
      (node (ref "J8") (pin "B8") (pinfunction "SBU2_B8") (pintype "passive"))
    )
    (net (code "41") (name "unconnected-(U1-~{STAT1}-Pad10)") (class "Default")
      (node (ref "U1") (pin "10") (pinfunction "~{STAT1}_10") (pintype "passive"))
    )
    (net (code "42") (name "unconnected-(U2-NC-Pad2)") (class "Default")
      (node (ref "U2") (pin "2") (pinfunction "NC_2") (pintype "passive"))
    )
  )
)
